# spirit1_433.net
KiCad netlist of a schematic drawn in Altium Designer
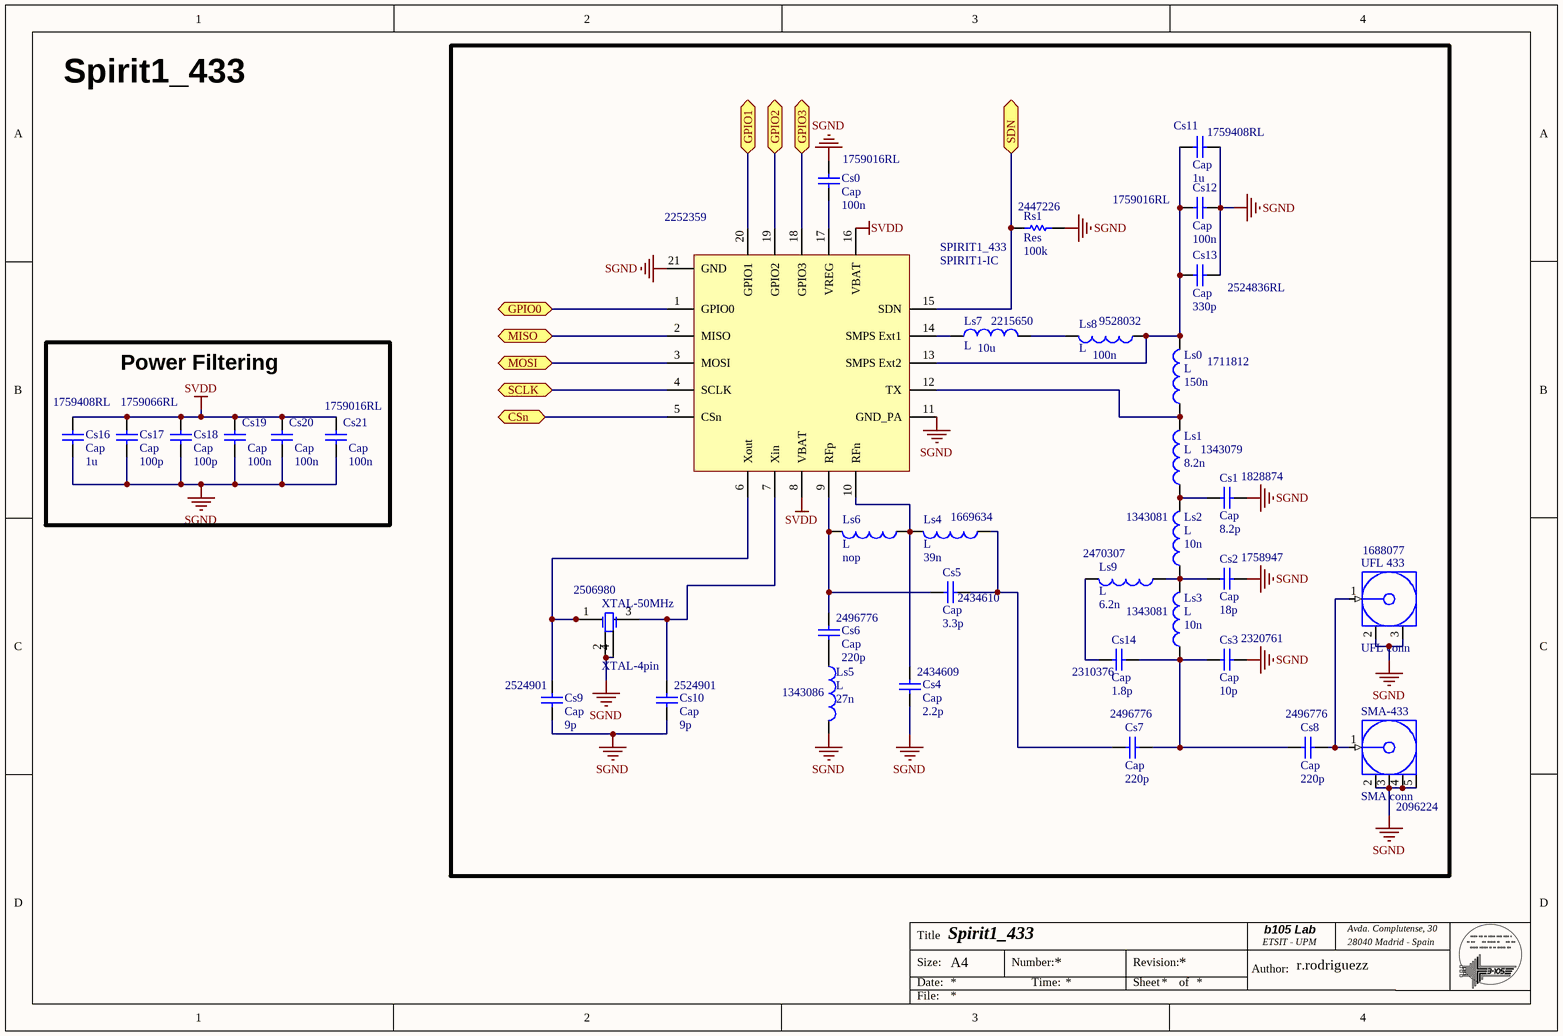
[diagram p0: spirit1_433.SchDoc]

(export (version "E")
  (design (tool "Eeschema 10.0.6"))
  (components
    (comp (ref "Cs0")
      (value "Cap")
      (footprint "0603 Cap")
      (fields
        (field (name "ALTIUM_VALUE") "100n")
        (field (name "SUPPLIER PART NUMBER 1") "1759016RL")
        (field (name "MANUFACTURER") "MULTICOMP")
        (field (name "MANUFACTURER PART NUMBER") "MC0603B104K160CT")
      )
      (libsource (lib "B105lib") (part "Cap"))
    )
    (comp (ref "Cs1")
      (value "Cap")
      (footprint "0402 CAP")
      (fields
        (field (name "ALTIUM_VALUE") "8.2p")
        (field (name "SUPPLIER PART NUMBER 1") "1828874")
        (field (name "MANUFACTURER") "MURATA")
        (field (name "MANUFACTURER PART NUMBER") "GRM1555C1H8R2CA01D")
      )
      (libsource (lib "B105lib") (part "Cap"))
    )
    (comp (ref "Cs2")
      (value "Cap")
      (footprint "0402 CAP")
      (fields
        (field (name "ALTIUM_VALUE") "18p")
        (field (name "SUPPLIER PART NUMBER 1") "1758947")
        (field (name "MANUFACTURER") "MULTICOMP")
        (field (name "MANUFACTURER PART NUMBER") "MC0402N180J500CT")
      )
      (libsource (lib "B105lib") (part "Cap"))
    )
    (comp (ref "Cs3")
      (value "Cap")
      (footprint "0402 CAP")
      (fields
        (field (name "ALTIUM_VALUE") "10p")
        (field (name "SUPPLIER PART NUMBER 1") "2320761")
        (field (name "MANUFACTURER") "MULTICOMP")
        (field (name "MANUFACTURER PART NUMBER") "MC0402N100J500CT")
      )
      (libsource (lib "B105lib") (part "Cap"))
    )
    (comp (ref "Cs4")
      (value "Cap")
      (footprint "0402 CAP")
      (fields
        (field (name "ALTIUM_VALUE") "2.2p")
        (field (name "SUPPLIER PART NUMBER 1") "2434609")
        (field (name "MANUFACTURER") "MURATA")
        (field (name "MANUFACTURER PART NUMBER") "GRM1555C1H2R2CA01D")
      )
      (libsource (lib "B105lib") (part "Cap"))
    )
    (comp (ref "Cs5")
      (value "Cap")
      (footprint "0402 CAP")
      (fields
        (field (name "ALTIUM_VALUE") "3.3p")
        (field (name "SUPPLIER PART NUMBER 1") "2434610")
        (field (name "MANUFACTURER") "MURATA")
        (field (name "MANUFACTURER PART NUMBER") "GRM1555C1H3R3CA01D")
      )
      (libsource (lib "B105lib") (part "Cap"))
    )
    (comp (ref "Cs6")
      (value "Cap")
      (footprint "0402 CAP")
      (fields
        (field (name "ALTIUM_VALUE") "220p")
        (field (name "SUPPLIER PART NUMBER 1") "2496776")
        (field (name "MANUFACTURER") "WALSIN")
        (field (name "MANUFACTURER PART NUMBER") "0402B221K500CT")
      )
      (libsource (lib "B105lib") (part "Cap"))
    )
    (comp (ref "Cs7")
      (value "Cap")
      (footprint "0402 CAP")
      (fields
        (field (name "ALTIUM_VALUE") "220p")
        (field (name "SUPPLIER PART NUMBER 1") "2496776")
        (field (name "MANUFACTURER") "WALSIN")
        (field (name "MANUFACTURER PART NUMBER") "0402B221K500CT")
      )
      (libsource (lib "B105lib") (part "Cap"))
    )
    (comp (ref "Cs8")
      (value "Cap")
      (footprint "0402 CAP")
      (fields
        (field (name "ALTIUM_VALUE") "220p")
        (field (name "SUPPLIER PART NUMBER 1") "2496776")
        (field (name "MANUFACTURER") "WALSIN")
        (field (name "MANUFACTURER PART NUMBER") "0402B221K500CT")
      )
      (libsource (lib "B105lib") (part "Cap"))
    )
    (comp (ref "Cs9")
      (value "Cap")
      (footprint "0603 Cap")
      (fields
        (field (name "ALTIUM_VALUE") "9p")
        (field (name "SUPPLIER PART NUMBER 1") "2524901")
        (field (name "MANUFACTURER") "WALSIN")
        (field (name "MANUFACTURER PART NUMBER") "0603N9R0D500CT")
      )
      (libsource (lib "B105lib") (part "Cap"))
    )
    (comp (ref "Cs10")
      (value "Cap")
      (footprint "0603 Cap")
      (fields
        (field (name "ALTIUM_VALUE") "9p")
        (field (name "SUPPLIER PART NUMBER 1") "2524901")
        (field (name "MANUFACTURER") "WALSIN")
        (field (name "MANUFACTURER PART NUMBER") "0603N9R0D500CT")
      )
      (libsource (lib "B105lib") (part "Cap"))
    )
    (comp (ref "Cs11")
      (value "Cap")
      (footprint "0603 Cap")
      (fields
        (field (name "ALTIUM_VALUE") "1u")
        (field (name "SUPPLIER PART NUMBER 1") "1759408RL")
        (field (name "MANUFACTURER") "MULTICOMP")
        (field (name "MANUFACTURER PART NUMBER") "MC0603F105Z160CT")
      )
      (libsource (lib "B105lib") (part "Cap"))
    )
    (comp (ref "Cs12")
      (value "Cap")
      (footprint "0603 Cap")
      (fields
        (field (name "ALTIUM_VALUE") "100n")
        (field (name "SUPPLIER PART NUMBER 1") "1759016RL")
        (field (name "MANUFACTURER") "MULTICOMP")
        (field (name "MANUFACTURER PART NUMBER") "MC0603B104K160CT")
      )
      (libsource (lib "B105lib") (part "Cap"))
    )
    (comp (ref "Cs13")
      (value "Cap")
      (footprint "0603 Cap")
      (fields
        (field (name "ALTIUM_VALUE") "330p")
        (field (name "SUPPLIER PART NUMBER 1") "2524836RL")
        (field (name "MANUFACTURER") "WALSIN")
        (field (name "MANUFACTURER PART NUMBER") "0603B331K500CT")
      )
      (libsource (lib "B105lib") (part "Cap"))
    )
    (comp (ref "Cs14")
      (value "Cap")
      (footprint "0402 CAP")
      (fields
        (field (name "ALTIUM_VALUE") "1.8p")
        (field (name "SUPPLIER PART NUMBER 1") "2310376")
        (field (name "MANUFACTURER") "MULTICOMP")
        (field (name "MANUFACTURER PART NUMBER") "MCRF15N1R8A500CT")
      )
      (libsource (lib "B105lib") (part "Cap"))
    )
    (comp (ref "Cs16")
      (value "Cap")
      (footprint "0603 Cap")
      (fields
        (field (name "ALTIUM_VALUE") "1u")
        (field (name "SUPPLIER PART NUMBER 1") "1759408RL")
        (field (name "MANUFACTURER") "MULTICOMP")
        (field (name "MANUFACTURER PART NUMBER") "MC0603F105Z160CT")
      )
      (libsource (lib "B105lib") (part "Cap"))
    )
    (comp (ref "Cs17")
      (value "Cap")
      (footprint "0603 Cap")
      (fields
        (field (name "ALTIUM_VALUE") "100p")
        (field (name "SUPPLIER PART NUMBER 1") "1759066RL")
        (field (name "MANUFACTURER") "MULTICOMP")
        (field (name "MANUFACTURER PART NUMBER") "MC0603N101J500CT")
      )
      (libsource (lib "B105lib") (part "Cap"))
    )
    (comp (ref "Cs18")
      (value "Cap")
      (footprint "0603 Cap")
      (fields
        (field (name "ALTIUM_VALUE") "100p")
        (field (name "MANUFACTURER") "MULTICOMP")
        (field (name "MANUFACTURER PART NUMBER") "MC0603N101J500CT")
      )
      (libsource (lib "B105lib") (part "Cap"))
    )
    (comp (ref "Cs19")
      (value "Cap")
      (footprint "0603 Cap")
      (fields
        (field (name "ALTIUM_VALUE") "100n")
        (field (name "MANUFACTURER") "MULTICOMP")
        (field (name "MANUFACTURER PART NUMBER") "MC0603B104K160CT")
      )
      (libsource (lib "B105lib") (part "Cap"))
    )
    (comp (ref "Cs20")
      (value "Cap")
      (footprint "0603 Cap")
      (fields
        (field (name "ALTIUM_VALUE") "100n")
        (field (name "MANUFACTURER") "MULTICOMP")
        (field (name "MANUFACTURER PART NUMBER") "MC0603B104K160CT")
      )
      (libsource (lib "B105lib") (part "Cap"))
    )
    (comp (ref "Cs21")
      (value "Cap")
      (footprint "0603 Cap")
      (fields
        (field (name "ALTIUM_VALUE") "100n")
        (field (name "SUPPLIER PART NUMBER 1") "1759016RL")
        (field (name "MANUFACTURER") "MULTICOMP")
        (field (name "MANUFACTURER PART NUMBER") "MC0603B104K160CT")
      )
      (libsource (lib "B105lib") (part "Cap"))
    )
    (comp (ref "Ls0")
      (value "L")
      (footprint "0603 IND")
      (fields
        (field (name "ALTIUM_VALUE") "150n")
        (field (name "SUPPLIER PART NUMBER 1") "1711812")
        (field (name "MANUFACTURER") "MULTICOMP")
        (field (name "MANUFACTURER PART NUMBER") "MCFT000097")
      )
      (libsource (lib "B105lib") (part "Ind"))
    )
    (comp (ref "Ls1")
      (value "L")
      (footprint "0402 IND")
      (fields
        (field (name "ALTIUM_VALUE") "8.2n")
        (field (name "SUPPLIER PART NUMBER 1") "1343079")
        (field (name "MANUFACTURER") "MURATA")
        (field (name "MANUFACTURER PART NUMBER") "LQG15HN8N2J02D")
      )
      (libsource (lib "B105lib") (part "Ind"))
    )
    (comp (ref "Ls2")
      (value "L")
      (footprint "0402 IND")
      (fields
        (field (name "ALTIUM_VALUE") "10n")
        (field (name "SUPPLIER PART NUMBER 1") "1343081")
        (field (name "MANUFACTURER") "MURATA")
        (field (name "MANUFACTURER PART NUMBER") "LQG15HN10NJ02D")
      )
      (libsource (lib "B105lib") (part "Ind"))
    )
    (comp (ref "Ls3")
      (value "L")
      (footprint "0402 IND")
      (fields
        (field (name "ALTIUM_VALUE") "10n")
        (field (name "SUPPLIER PART NUMBER 1") "1343081")
        (field (name "MANUFACTURER") "MURATA")
        (field (name "MANUFACTURER PART NUMBER") "LQG15HN10NJ02D")
      )
      (libsource (lib "B105lib") (part "Ind"))
    )
    (comp (ref "Ls4")
      (value "L")
      (footprint "0402 IND")
      (fields
        (field (name "ALTIUM_VALUE") "39n")
        (field (name "SUPPLIER PART NUMBER 1") "1669634")
        (field (name "MANUFACTURER") "TDK")
        (field (name "MANUFACTURER PART NUMBER") "MLK1005S39NJ")
      )
      (libsource (lib "B105lib") (part "Ind"))
    )
    (comp (ref "Ls5")
      (value "L")
      (footprint "0402 IND")
      (fields
        (field (name "ALTIUM_VALUE") "27n")
        (field (name "SUPPLIER PART NUMBER 1") "1343086")
        (field (name "MANUFACTURER") "MURATA")
        (field (name "MANUFACTURER PART NUMBER") "LQG15HN27NJ02D")
      )
      (libsource (lib "B105lib") (part "Ind"))
    )
    (comp (ref "Ls6")
      (value "L")
      (footprint "0402 IND")
      (fields (field (name "ALTIUM_VALUE") "nop"))
      (libsource (lib "B105lib") (part "Ind"))
    )
    (comp (ref "Ls7")
      (value "L")
      (footprint "0805 Ind")
      (fields
        (field (name "ALTIUM_VALUE") "10u")
        (field (name "SUPPLIER PART NUMBER 1") "2215650")
        (field (name "MANUFACTURER") "TDK")
        (field (name "MANUFACTURER PART NUMBER") "MLZ2012M100WT")
      )
      (libsource (lib "B105lib") (part "Ind"))
    )
    (comp (ref "Ls8")
      (value "L")
      (footprint "0603 IND")
      (fields
        (field (name "ALTIUM_VALUE") "100n")
        (field (name "SUPPLIER PART NUMBER 1") "9528032")
        (field (name "MANUFACTURER") "MURATA")
        (field (name "MANUFACTURER PART NUMBER") "LQW18ANR10G00D")
      )
      (libsource (lib "B105lib") (part "Ind"))
    )
    (comp (ref "Ls9")
      (value "L")
      (footprint "0402 IND")
      (fields
        (field (name "ALTIUM_VALUE") "6.2n")
        (field (name "SUPPLIER PART NUMBER 1") "2470307")
        (field (name "MANUFACTURER") "MURATA")
        (field (name "MANUFACTURER PART NUMBER") "LQW15AN6N2B00D")
      )
      (libsource (lib "B105lib") (part "Ind"))
    )
    (comp (ref "Rs1")
      (value "Res")
      (footprint "0603 Res")
      (fields
        (field (name "ALTIUM_VALUE") "100k")
        (field (name "SUPPLIER PART NUMBER 1") "2447226")
        (field (name "MANUFACTURER") "MULTICOMP")
        (field (name "MANUFACTURER PART NUMBER") "MCWR06X1003FTL")
      )
      (libsource (lib "B105lib") (part "Res"))
    )
    (comp (ref "SMA-433")
      (value "SMA conn")
      (footprint "SMA-conn")
      (fields
        (field (name "SUPPLIER PART NUMBER 1") "2096224")
        (field (name "MANUFACTURER") "LPRS")
        (field (name "MANUFACTURER PART NUMBER") "SMA RA CONNECTOR")
      )
      (libsource (lib "B105lib") (part "SMA conn"))
    )
    (comp (ref "SPIRIT1_433")
      (value "SPIRIT1-IC")
      (footprint "QFN-20")
      (fields
        (field (name "SUPPLIER PART NUMBER 1") "2252359")
        (field (name "MANUFACTURER") "STMICROELECTRONICS")
        (field (name "MANUFACTURER PART NUMBER") "SPIRIT1QTR")
      )
      (libsource (lib "B105lib") (part "SPIRIT1-IC"))
    )
    (comp (ref "UFL 433")
      (value "UFL conn")
      (footprint "UFL conn")
      (fields
        (field (name "SUPPLIER PART NUMBER 1") "1688077")
        (field (name "MANUFACTURER") "HIROSE(HRS)")
        (field (name "MANUFACTURER PART NUMBER") "U.FL-R-SMT-1(10)")
      )
      (libsource (lib "B105lib") (part "UFL conn"))
    )
    (comp (ref "XTAL-50MHz")
      (value "XTAL-4pin")
      (footprint "XTAL-4PIN-2mmx1.6mm")
      (fields
        (field (name "SUPPLIER PART NUMBER 1") "2506980")
        (field (name "MANUFACTURER") "EPSON")
        (field (name "MANUFACTURER PART NUMBER") "X1E000351002812")
      )
      (libsource (lib "B105lib") (part "XTAL-4pin"))
    )
  )
  (nets
    (net (code "1") (name "/CSn") (class "Default")
      (node (ref "SPIRIT1_433") (pin "5") (pinfunction "CSn_5") (pintype "passive"))
    )
    (net (code "2") (name "/GPIO0") (class "Default")
      (node (ref "SPIRIT1_433") (pin "1") (pinfunction "GPIO0_1") (pintype "passive"))
    )
    (net (code "3") (name "/GPIO1") (class "Default")
      (node (ref "SPIRIT1_433") (pin "20") (pinfunction "GPIO1_20") (pintype "passive"))
    )
    (net (code "4") (name "/GPIO2") (class "Default")
      (node (ref "SPIRIT1_433") (pin "19") (pinfunction "GPIO2_19") (pintype "passive"))
    )
    (net (code "5") (name "/GPIO3") (class "Default")
      (node (ref "SPIRIT1_433") (pin "18") (pinfunction "GPIO3_18") (pintype "passive"))
    )
    (net (code "6") (name "/MISO") (class "Default")
      (node (ref "SPIRIT1_433") (pin "2") (pinfunction "MISO_2") (pintype "passive"))
    )
    (net (code "7") (name "/MOSI") (class "Default")
      (node (ref "SPIRIT1_433") (pin "3") (pinfunction "MOSI_3") (pintype "passive"))
    )
    (net (code "8") (name "/SCLK") (class "Default")
      (node (ref "SPIRIT1_433") (pin "4") (pinfunction "SCLK_4") (pintype "passive"))
    )
    (net (code "9") (name "/SDN") (class "Default")
      (node (ref "Rs1") (pin "1") (pinfunction "1_1") (pintype "passive"))
      (node (ref "SPIRIT1_433") (pin "15") (pinfunction "SDN_15") (pintype "passive"))
    )
    (net (code "10") (name "Net-(Cs1-Pad2)") (class "Default")
      (node (ref "Cs1") (pin "2") (pinfunction "2_2") (pintype "passive"))
      (node (ref "Ls1") (pin "1") (pinfunction "1_1") (pintype "passive"))
      (node (ref "Ls2") (pin "2") (pinfunction "2_2") (pintype "passive"))
    )
    (net (code "11") (name "Net-(Cs2-Pad2)") (class "Default")
      (node (ref "Cs2") (pin "2") (pinfunction "2_2") (pintype "passive"))
      (node (ref "Ls2") (pin "1") (pinfunction "1_1") (pintype "passive"))
      (node (ref "Ls3") (pin "2") (pinfunction "2_2") (pintype "passive"))
      (node (ref "Ls9") (pin "1") (pinfunction "1_1") (pintype "passive"))
    )
    (net (code "12") (name "Net-(Cs5-Pad1)") (class "Default")
      (node (ref "Cs5") (pin "1") (pinfunction "1_1") (pintype "passive"))
      (node (ref "Cs7") (pin "1") (pinfunction "1_1") (pintype "passive"))
      (node (ref "Ls4") (pin "1") (pinfunction "1_1") (pintype "passive"))
    )
    (net (code "13") (name "Net-(Cs6-Pad2)") (class "Default")
      (node (ref "Cs6") (pin "2") (pinfunction "2_2") (pintype "passive"))
      (node (ref "Ls5") (pin "1") (pinfunction "1_1") (pintype "passive"))
    )
    (net (code "14") (name "Net-(Cs14-Pad1)") (class "Default")
      (node (ref "Cs14") (pin "1") (pinfunction "1_1") (pintype "passive"))
      (node (ref "Cs3") (pin "2") (pinfunction "2_2") (pintype "passive"))
      (node (ref "Cs7") (pin "2") (pinfunction "2_2") (pintype "passive"))
      (node (ref "Cs8") (pin "1") (pinfunction "1_1") (pintype "passive"))
      (node (ref "Ls3") (pin "1") (pinfunction "1_1") (pintype "passive"))
    )
    (net (code "15") (name "Net-(Cs14-Pad2)") (class "Default")
      (node (ref "Cs14") (pin "2") (pinfunction "2_2") (pintype "passive"))
      (node (ref "Ls9") (pin "2") (pinfunction "2_2") (pintype "passive"))
    )
    (net (code "16") (name "Net-(Ls7-Pad2)") (class "Default")
      (node (ref "Ls7") (pin "2") (pinfunction "2_2") (pintype "passive"))
      (node (ref "Ls8") (pin "2") (pinfunction "2_2") (pintype "passive"))
    )
    (net (code "17") (name "Net-(SMA-433-Signal)") (class "Default")
      (node (ref "Cs8") (pin "2") (pinfunction "2_2") (pintype "passive"))
      (node (ref "SMA-433") (pin "1") (pinfunction "Signal_1") (pintype "input"))
      (node (ref "UFL 433") (pin "1") (pinfunction "Signal_1") (pintype "input"))
    )
    (net (code "18") (name "Net-(SPIRIT1_433-RFn)") (class "Default")
      (node (ref "Cs4") (pin "2") (pinfunction "2_2") (pintype "passive"))
      (node (ref "Ls4") (pin "2") (pinfunction "2_2") (pintype "passive"))
      (node (ref "Ls6") (pin "1") (pinfunction "1_1") (pintype "passive"))
      (node (ref "SPIRIT1_433") (pin "10") (pinfunction "RFn_10") (pintype "passive"))
    )
    (net (code "19") (name "Net-(SPIRIT1_433-RFp)") (class "Default")
      (node (ref "Cs5") (pin "2") (pinfunction "2_2") (pintype "passive"))
      (node (ref "Cs6") (pin "1") (pinfunction "1_1") (pintype "passive"))
      (node (ref "Ls6") (pin "2") (pinfunction "2_2") (pintype "passive"))
      (node (ref "SPIRIT1_433") (pin "9") (pinfunction "RFp_9") (pintype "passive"))
    )
    (net (code "20") (name "Net-(SPIRIT1_433-SMPS_Ext1)") (class "Default")
      (node (ref "Ls7") (pin "1") (pinfunction "1_1") (pintype "passive"))
      (node (ref "SPIRIT1_433") (pin "14") (pinfunction "SMPS_Ext1_14") (pintype "passive"))
    )
    (net (code "21") (name "Net-(SPIRIT1_433-SMPS_Ext2)") (class "Default")
      (node (ref "Cs11") (pin "2") (pinfunction "2_2") (pintype "passive"))
      (node (ref "Cs12") (pin "2") (pinfunction "2_2") (pintype "passive"))
      (node (ref "Cs13") (pin "2") (pinfunction "2_2") (pintype "passive"))
      (node (ref "Ls0") (pin "2") (pinfunction "2_2") (pintype "passive"))
      (node (ref "Ls8") (pin "1") (pinfunction "1_1") (pintype "passive"))
      (node (ref "SPIRIT1_433") (pin "13") (pinfunction "SMPS_Ext2_13") (pintype "passive"))
    )
    (net (code "22") (name "Net-(SPIRIT1_433-TX)") (class "Default")
      (node (ref "Ls0") (pin "1") (pinfunction "1_1") (pintype "passive"))
      (node (ref "Ls1") (pin "2") (pinfunction "2_2") (pintype "passive"))
      (node (ref "SPIRIT1_433") (pin "12") (pinfunction "TX_12") (pintype "passive"))
    )
    (net (code "23") (name "Net-(SPIRIT1_433-VREG)") (class "Default")
      (node (ref "Cs0") (pin "1") (pinfunction "1_1") (pintype "passive"))
      (node (ref "SPIRIT1_433") (pin "17") (pinfunction "VREG_17") (pintype "passive"))
    )
    (net (code "24") (name "Net-(SPIRIT1_433-Xin)") (class "Default")
      (node (ref "Cs10") (pin "2") (pinfunction "2_2") (pintype "passive"))
      (node (ref "SPIRIT1_433") (pin "7") (pinfunction "Xin_7") (pintype "passive"))
      (node (ref "XTAL-50MHz") (pin "3") (pinfunction "OSC2_3") (pintype "passive"))
    )
    (net (code "25") (name "Net-(SPIRIT1_433-Xout)") (class "Default")
      (node (ref "Cs9") (pin "2") (pinfunction "2_2") (pintype "passive"))
      (node (ref "SPIRIT1_433") (pin "6") (pinfunction "Xout_6") (pintype "passive"))
      (node (ref "XTAL-50MHz") (pin "1") (pinfunction "OSC1_1") (pintype "passive"))
    )
    (net (code "26") (name "SGND") (class "Default")
      (node (ref "Cs0") (pin "2") (pinfunction "2_2") (pintype "passive"))
      (node (ref "Cs1") (pin "1") (pinfunction "1_1") (pintype "passive"))
      (node (ref "Cs10") (pin "1") (pinfunction "1_1") (pintype "passive"))
      (node (ref "Cs11") (pin "1") (pinfunction "1_1") (pintype "passive"))
      (node (ref "Cs12") (pin "1") (pinfunction "1_1") (pintype "passive"))
      (node (ref "Cs13") (pin "1") (pinfunction "1_1") (pintype "passive"))
      (node (ref "Cs16") (pin "1") (pinfunction "1_1") (pintype "passive"))
      (node (ref "Cs17") (pin "1") (pinfunction "1_1") (pintype "passive"))
      (node (ref "Cs18") (pin "1") (pinfunction "1_1") (pintype "passive"))
      (node (ref "Cs19") (pin "1") (pinfunction "1_1") (pintype "passive"))
      (node (ref "Cs2") (pin "1") (pinfunction "1_1") (pintype "passive"))
      (node (ref "Cs20") (pin "1") (pinfunction "1_1") (pintype "passive"))
      (node (ref "Cs21") (pin "1") (pinfunction "1_1") (pintype "passive"))
      (node (ref "Cs3") (pin "1") (pinfunction "1_1") (pintype "passive"))
      (node (ref "Cs4") (pin "1") (pinfunction "1_1") (pintype "passive"))
      (node (ref "Cs9") (pin "1") (pinfunction "1_1") (pintype "passive"))
      (node (ref "Ls5") (pin "2") (pinfunction "2_2") (pintype "passive"))
      (node (ref "Rs1") (pin "2") (pinfunction "2_2") (pintype "passive"))
      (node (ref "SMA-433") (pin "2") (pinfunction "GND_2") (pintype "power_in"))
      (node (ref "SMA-433") (pin "3") (pinfunction "GND_3") (pintype "power_in"))
      (node (ref "SMA-433") (pin "4") (pinfunction "GND_4") (pintype "power_in"))
      (node (ref "SMA-433") (pin "5") (pinfunction "GND_5") (pintype "power_in"))
      (node (ref "SPIRIT1_433") (pin "11") (pinfunction "GND_PA_11") (pintype "passive"))
      (node (ref "SPIRIT1_433") (pin "21") (pinfunction "GND_21") (pintype "passive"))
      (node (ref "UFL 433") (pin "2") (pinfunction "GND_2") (pintype "power_in"))
      (node (ref "UFL 433") (pin "3") (pinfunction "GND_3") (pintype "power_in"))
      (node (ref "XTAL-50MHz") (pin "2") (pinfunction "GND_2") (pintype "passive"))
      (node (ref "XTAL-50MHz") (pin "4") (pinfunction "GND_4") (pintype "passive"))
    )
    (net (code "27") (name "SVDD") (class "Default")
      (node (ref "Cs16") (pin "2") (pinfunction "2_2") (pintype "passive"))
      (node (ref "Cs17") (pin "2") (pinfunction "2_2") (pintype "passive"))
      (node (ref "Cs18") (pin "2") (pinfunction "2_2") (pintype "passive"))
      (node (ref "Cs19") (pin "2") (pinfunction "2_2") (pintype "passive"))
      (node (ref "Cs20") (pin "2") (pinfunction "2_2") (pintype "passive"))
      (node (ref "Cs21") (pin "2") (pinfunction "2_2") (pintype "passive"))
      (node (ref "SPIRIT1_433") (pin "16") (pinfunction "VBAT_16") (pintype "passive"))
      (node (ref "SPIRIT1_433") (pin "8") (pinfunction "VBAT_8") (pintype "passive"))
    )
  )
)
